# bigboard.net
KiCad netlist of a schematic drawn in EAGLE
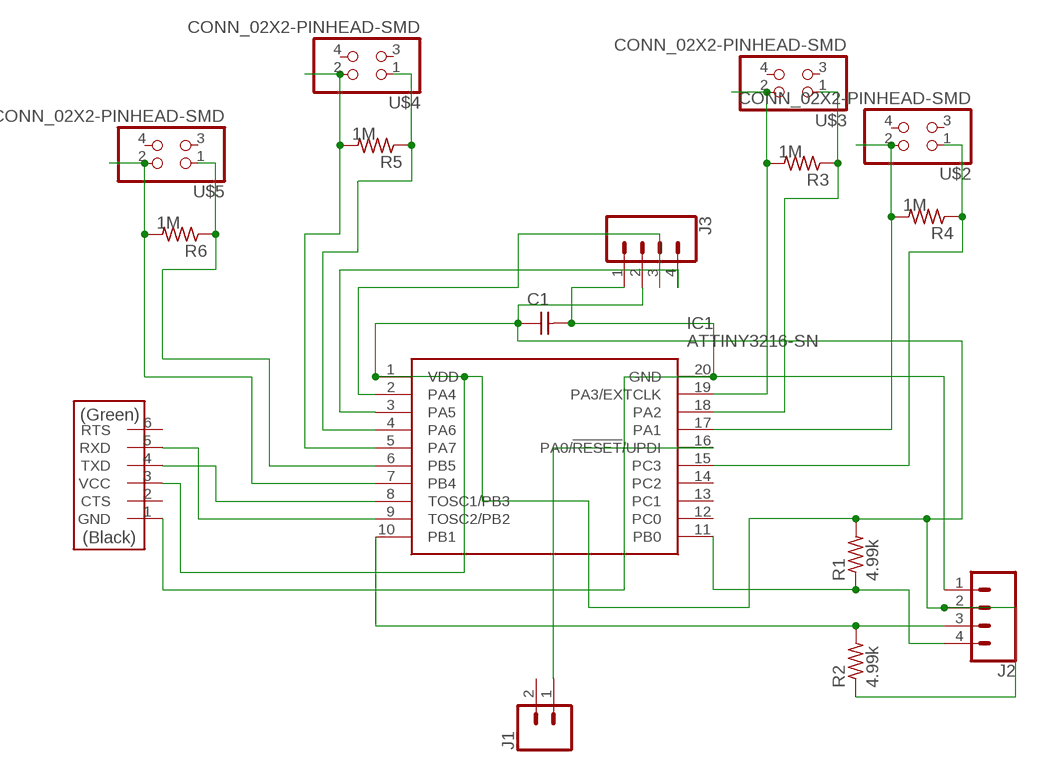
[diagram p0: schematic, sheet 1]

(export (version "E")
  (design (tool "Eeschema 10.0.6"))
  (components
    (comp (ref "C1")
      (value "CAP_UNPOLARIZEDFAB")
      (footprint "eagle-import:C1206FAB")
      (libsource (lib "eagle-import") (part "CAP_UNPOLARIZEDFAB"))
    )
    (comp (ref "IC1")
      (value "ATTINY3216-SN")
      (footprint "eagle-import:SOIC127P1030X265-20N")
      (fields (field (name "MF") "Microchip Technology"))
      (libsource (lib "eagle-import") (part "ATTINY3216-SN"))
    )
    (comp (ref "J1")
      (value "CONN_02LOCK_LONGPADS")
      (footprint "eagle-import:1X02_LOCK_LONGPADS")
      (libsource (lib "eagle-import") (part "CONN_02LOCK_LONGPADS"))
    )
    (comp (ref "J2")
      (value "CONN_04SMD_LONG")
      (footprint "eagle-import:1X04_SMD_LONG")
      (libsource (lib "eagle-import") (part "CONN_04SMD_LONG"))
    )
    (comp (ref "J3")
      (value "CONN_04SMD_LONG")
      (footprint "eagle-import:1X04_SMD_LONG")
      (libsource (lib "eagle-import") (part "CONN_04SMD_LONG"))
    )
    (comp (ref "R1")
      (value "4.99k")
      (footprint "eagle-import:R1206FAB")
      (libsource (lib "eagle-import") (part "R1206FAB"))
    )
    (comp (ref "R2")
      (value "4.99k")
      (footprint "eagle-import:R1206FAB")
      (libsource (lib "eagle-import") (part "R1206FAB"))
    )
    (comp (ref "R3")
      (value "R1206FAB")
      (footprint "eagle-import:R1206FAB")
      (fields (field (name "R1") "1M"))
      (libsource (lib "eagle-import") (part "R1206FAB"))
    )
    (comp (ref "R4")
      (value "R1206FAB")
      (footprint "eagle-import:R1206FAB")
      (fields (field (name "R1") "1M"))
      (libsource (lib "eagle-import") (part "R1206FAB"))
    )
    (comp (ref "R5")
      (value "R1206FAB")
      (footprint "eagle-import:R1206FAB")
      (fields (field (name "R1") "1M"))
      (libsource (lib "eagle-import") (part "R1206FAB"))
    )
    (comp (ref "R6")
      (value "R1206FAB")
      (footprint "eagle-import:R1206FAB")
      (fields (field (name "R1") "1M"))
      (libsource (lib "eagle-import") (part "R1206FAB"))
    )
    (comp (ref "U$1")
      (value "CONN_06_FTDI-SMD-HEADER")
      (footprint "eagle-import:1X06SMD")
      (libsource (lib "eagle-import") (part "CONN_06_FTDI-SMD-HEADER"))
    )
    (comp (ref "U$2")
      (value "CONN_02X2-PINHEAD-SMD")
      (footprint "eagle-import:2X02SMD")
      (libsource (lib "eagle-import") (part "CONN_02X2-PINHEAD-SMD"))
    )
    (comp (ref "U$3")
      (value "CONN_02X2-PINHEAD-SMD")
      (footprint "eagle-import:2X02SMD")
      (libsource (lib "eagle-import") (part "CONN_02X2-PINHEAD-SMD"))
    )
    (comp (ref "U$4")
      (value "CONN_02X2-PINHEAD-SMD")
      (footprint "eagle-import:2X02SMD")
      (libsource (lib "eagle-import") (part "CONN_02X2-PINHEAD-SMD"))
    )
    (comp (ref "U$5")
      (value "CONN_02X2-PINHEAD-SMD")
      (footprint "eagle-import:2X02SMD")
      (libsource (lib "eagle-import") (part "CONN_02X2-PINHEAD-SMD"))
    )
  )
  (nets
    (net (code "1") (name "Net-(IC1-GND)") (class "Default")
      (node (ref "C1") (pin "2") (pinfunction "2_2") (pintype "passive"))
      (node (ref "IC1") (pin "20") (pinfunction "GND_20") (pintype "bidirectional"))
      (node (ref "J2") (pin "1") (pinfunction "1_1") (pintype "passive"))
      (node (ref "J3") (pin "1") (pinfunction "1_1") (pintype "passive"))
      (node (ref "U$1") (pin "1") (pinfunction "GND_1") (pintype "bidirectional"))
    )
    (net (code "2") (name "Net-(IC1-PA0{slash}~{RESET}{slash}UPDI)") (class "Default")
      (node (ref "IC1") (pin "16") (pinfunction "PA0/~{RESET}/UPDI_16") (pintype "bidirectional"))
      (node (ref "J1") (pin "1") (pinfunction "1_1") (pintype "passive"))
    )
    (net (code "3") (name "Net-(IC1-PA1)") (class "Default")
      (node (ref "IC1") (pin "17") (pinfunction "PA1_17") (pintype "bidirectional"))
      (node (ref "R4") (pin "2") (pinfunction "2_2") (pintype "passive"))
      (node (ref "U$2") (pin "2") (pinfunction "2_2") (pintype "passive"))
    )
    (net (code "4") (name "Net-(IC1-PA2)") (class "Default")
      (node (ref "IC1") (pin "18") (pinfunction "PA2_18") (pintype "bidirectional"))
      (node (ref "R3") (pin "1") (pinfunction "1_1") (pintype "passive"))
      (node (ref "U$3") (pin "1") (pinfunction "1_1") (pintype "passive"))
    )
    (net (code "5") (name "Net-(IC1-PA3{slash}EXTCLK)") (class "Default")
      (node (ref "IC1") (pin "19") (pinfunction "PA3/EXTCLK_19") (pintype "bidirectional"))
      (node (ref "R3") (pin "2") (pinfunction "2_2") (pintype "passive"))
      (node (ref "U$3") (pin "2") (pinfunction "2_2") (pintype "passive"))
    )
    (net (code "6") (name "Net-(IC1-PA4)") (class "Default")
      (node (ref "IC1") (pin "2") (pinfunction "PA4_2") (pintype "bidirectional"))
      (node (ref "J3") (pin "3") (pinfunction "3_3") (pintype "passive"))
    )
    (net (code "7") (name "Net-(IC1-PA5)") (class "Default")
      (node (ref "IC1") (pin "3") (pinfunction "PA5_3") (pintype "bidirectional"))
      (node (ref "J3") (pin "4") (pinfunction "4_4") (pintype "passive"))
    )
    (net (code "8") (name "Net-(IC1-PA6)") (class "Default")
      (node (ref "IC1") (pin "4") (pinfunction "PA6_4") (pintype "bidirectional"))
      (node (ref "R5") (pin "1") (pinfunction "1_1") (pintype "passive"))
      (node (ref "U$4") (pin "1") (pinfunction "1_1") (pintype "passive"))
    )
    (net (code "9") (name "Net-(IC1-PA7)") (class "Default")
      (node (ref "IC1") (pin "5") (pinfunction "PA7_5") (pintype "bidirectional"))
      (node (ref "R5") (pin "2") (pinfunction "2_2") (pintype "passive"))
      (node (ref "U$4") (pin "2") (pinfunction "2_2") (pintype "passive"))
    )
    (net (code "10") (name "Net-(IC1-PB0)") (class "Default")
      (node (ref "IC1") (pin "11") (pinfunction "PB0_11") (pintype "bidirectional"))
      (node (ref "J2") (pin "4") (pinfunction "4_4") (pintype "passive"))
      (node (ref "R1") (pin "1") (pinfunction "1_1") (pintype "passive"))
    )
    (net (code "11") (name "Net-(IC1-PB1)") (class "Default")
      (node (ref "IC1") (pin "10") (pinfunction "PB1_10") (pintype "bidirectional"))
      (node (ref "J2") (pin "3") (pinfunction "3_3") (pintype "passive"))
      (node (ref "R2") (pin "2") (pinfunction "2_2") (pintype "passive"))
    )
    (net (code "12") (name "Net-(IC1-PB4)") (class "Default")
      (node (ref "IC1") (pin "7") (pinfunction "PB4_7") (pintype "bidirectional"))
      (node (ref "R6") (pin "2") (pinfunction "2_2") (pintype "passive"))
      (node (ref "U$5") (pin "2") (pinfunction "2_2") (pintype "passive"))
    )
    (net (code "13") (name "Net-(IC1-PB5)") (class "Default")
      (node (ref "IC1") (pin "6") (pinfunction "PB5_6") (pintype "bidirectional"))
      (node (ref "R6") (pin "1") (pinfunction "1_1") (pintype "passive"))
      (node (ref "U$5") (pin "1") (pinfunction "1_1") (pintype "passive"))
    )
    (net (code "14") (name "Net-(IC1-PC3)") (class "Default")
      (node (ref "IC1") (pin "15") (pinfunction "PC3_15") (pintype "bidirectional"))
      (node (ref "R4") (pin "1") (pinfunction "1_1") (pintype "passive"))
      (node (ref "U$2") (pin "1") (pinfunction "1_1") (pintype "passive"))
    )
    (net (code "15") (name "Net-(IC1-TOSC1{slash}PB3)") (class "Default")
      (node (ref "IC1") (pin "8") (pinfunction "TOSC1/PB3_8") (pintype "bidirectional"))
      (node (ref "U$1") (pin "4") (pinfunction "TXD_4") (pintype "bidirectional"))
    )
    (net (code "16") (name "Net-(IC1-TOSC2{slash}PB2)") (class "Default")
      (node (ref "IC1") (pin "9") (pinfunction "TOSC2/PB2_9") (pintype "bidirectional"))
      (node (ref "U$1") (pin "5") (pinfunction "RXD_5") (pintype "bidirectional"))
    )
    (net (code "17") (name "Net-(IC1-VDD)") (class "Default")
      (node (ref "C1") (pin "1") (pinfunction "1_1") (pintype "passive"))
      (node (ref "IC1") (pin "1") (pinfunction "VDD_1") (pintype "bidirectional"))
      (node (ref "J2") (pin "2") (pinfunction "2_2") (pintype "passive"))
      (node (ref "J3") (pin "2") (pinfunction "2_2") (pintype "passive"))
      (node (ref "R1") (pin "2") (pinfunction "2_2") (pintype "passive"))
      (node (ref "R2") (pin "1") (pinfunction "1_1") (pintype "passive"))
      (node (ref "U$1") (pin "3") (pinfunction "VCC_3") (pintype "bidirectional"))
    )
    (net (code "18") (name "unconnected-(IC1-PC0-Pad12)") (class "Default")
      (node (ref "IC1") (pin "12") (pinfunction "PC0_12") (pintype "bidirectional"))
    )
    (net (code "19") (name "unconnected-(IC1-PC1-Pad13)") (class "Default")
      (node (ref "IC1") (pin "13") (pinfunction "PC1_13") (pintype "bidirectional"))
    )
    (net (code "20") (name "unconnected-(IC1-PC2-Pad14)") (class "Default")
      (node (ref "IC1") (pin "14") (pinfunction "PC2_14") (pintype "bidirectional"))
    )
    (net (code "21") (name "unconnected-(J1-Pad2)") (class "Default")
      (node (ref "J1") (pin "2") (pinfunction "2_2") (pintype "passive"))
    )
    (net (code "22") (name "unconnected-(U$1-CTS-Pad2)") (class "Default")
      (node (ref "U$1") (pin "2") (pinfunction "CTS_2") (pintype "bidirectional"))
    )
    (net (code "23") (name "unconnected-(U$1-RTS-Pad6)") (class "Default")
      (node (ref "U$1") (pin "6") (pinfunction "RTS_6") (pintype "bidirectional"))
    )
    (net (code "24") (name "unconnected-(U$2-Pad3)") (class "Default")
      (node (ref "U$2") (pin "3") (pinfunction "3_3") (pintype "passive"))
    )
    (net (code "25") (name "unconnected-(U$2-Pad4)") (class "Default")
      (node (ref "U$2") (pin "4") (pinfunction "4_4") (pintype "passive"))
    )
    (net (code "26") (name "unconnected-(U$3-Pad3)") (class "Default")
      (node (ref "U$3") (pin "3") (pinfunction "3_3") (pintype "passive"))
    )
    (net (code "27") (name "unconnected-(U$3-Pad4)") (class "Default")
      (node (ref "U$3") (pin "4") (pinfunction "4_4") (pintype "passive"))
    )
    (net (code "28") (name "unconnected-(U$4-Pad3)") (class "Default")
      (node (ref "U$4") (pin "3") (pinfunction "3_3") (pintype "passive"))
    )
    (net (code "29") (name "unconnected-(U$4-Pad4)") (class "Default")
      (node (ref "U$4") (pin "4") (pinfunction "4_4") (pintype "passive"))
    )
    (net (code "30") (name "unconnected-(U$5-Pad3)") (class "Default")
      (node (ref "U$5") (pin "3") (pinfunction "3_3") (pintype "passive"))
    )
    (net (code "31") (name "unconnected-(U$5-Pad4)") (class "Default")
      (node (ref "U$5") (pin "4") (pinfunction "4_4") (pintype "passive"))
    )
  )
)
